# Linkee.net
KiCad netlist of a schematic drawn in EasyEDA
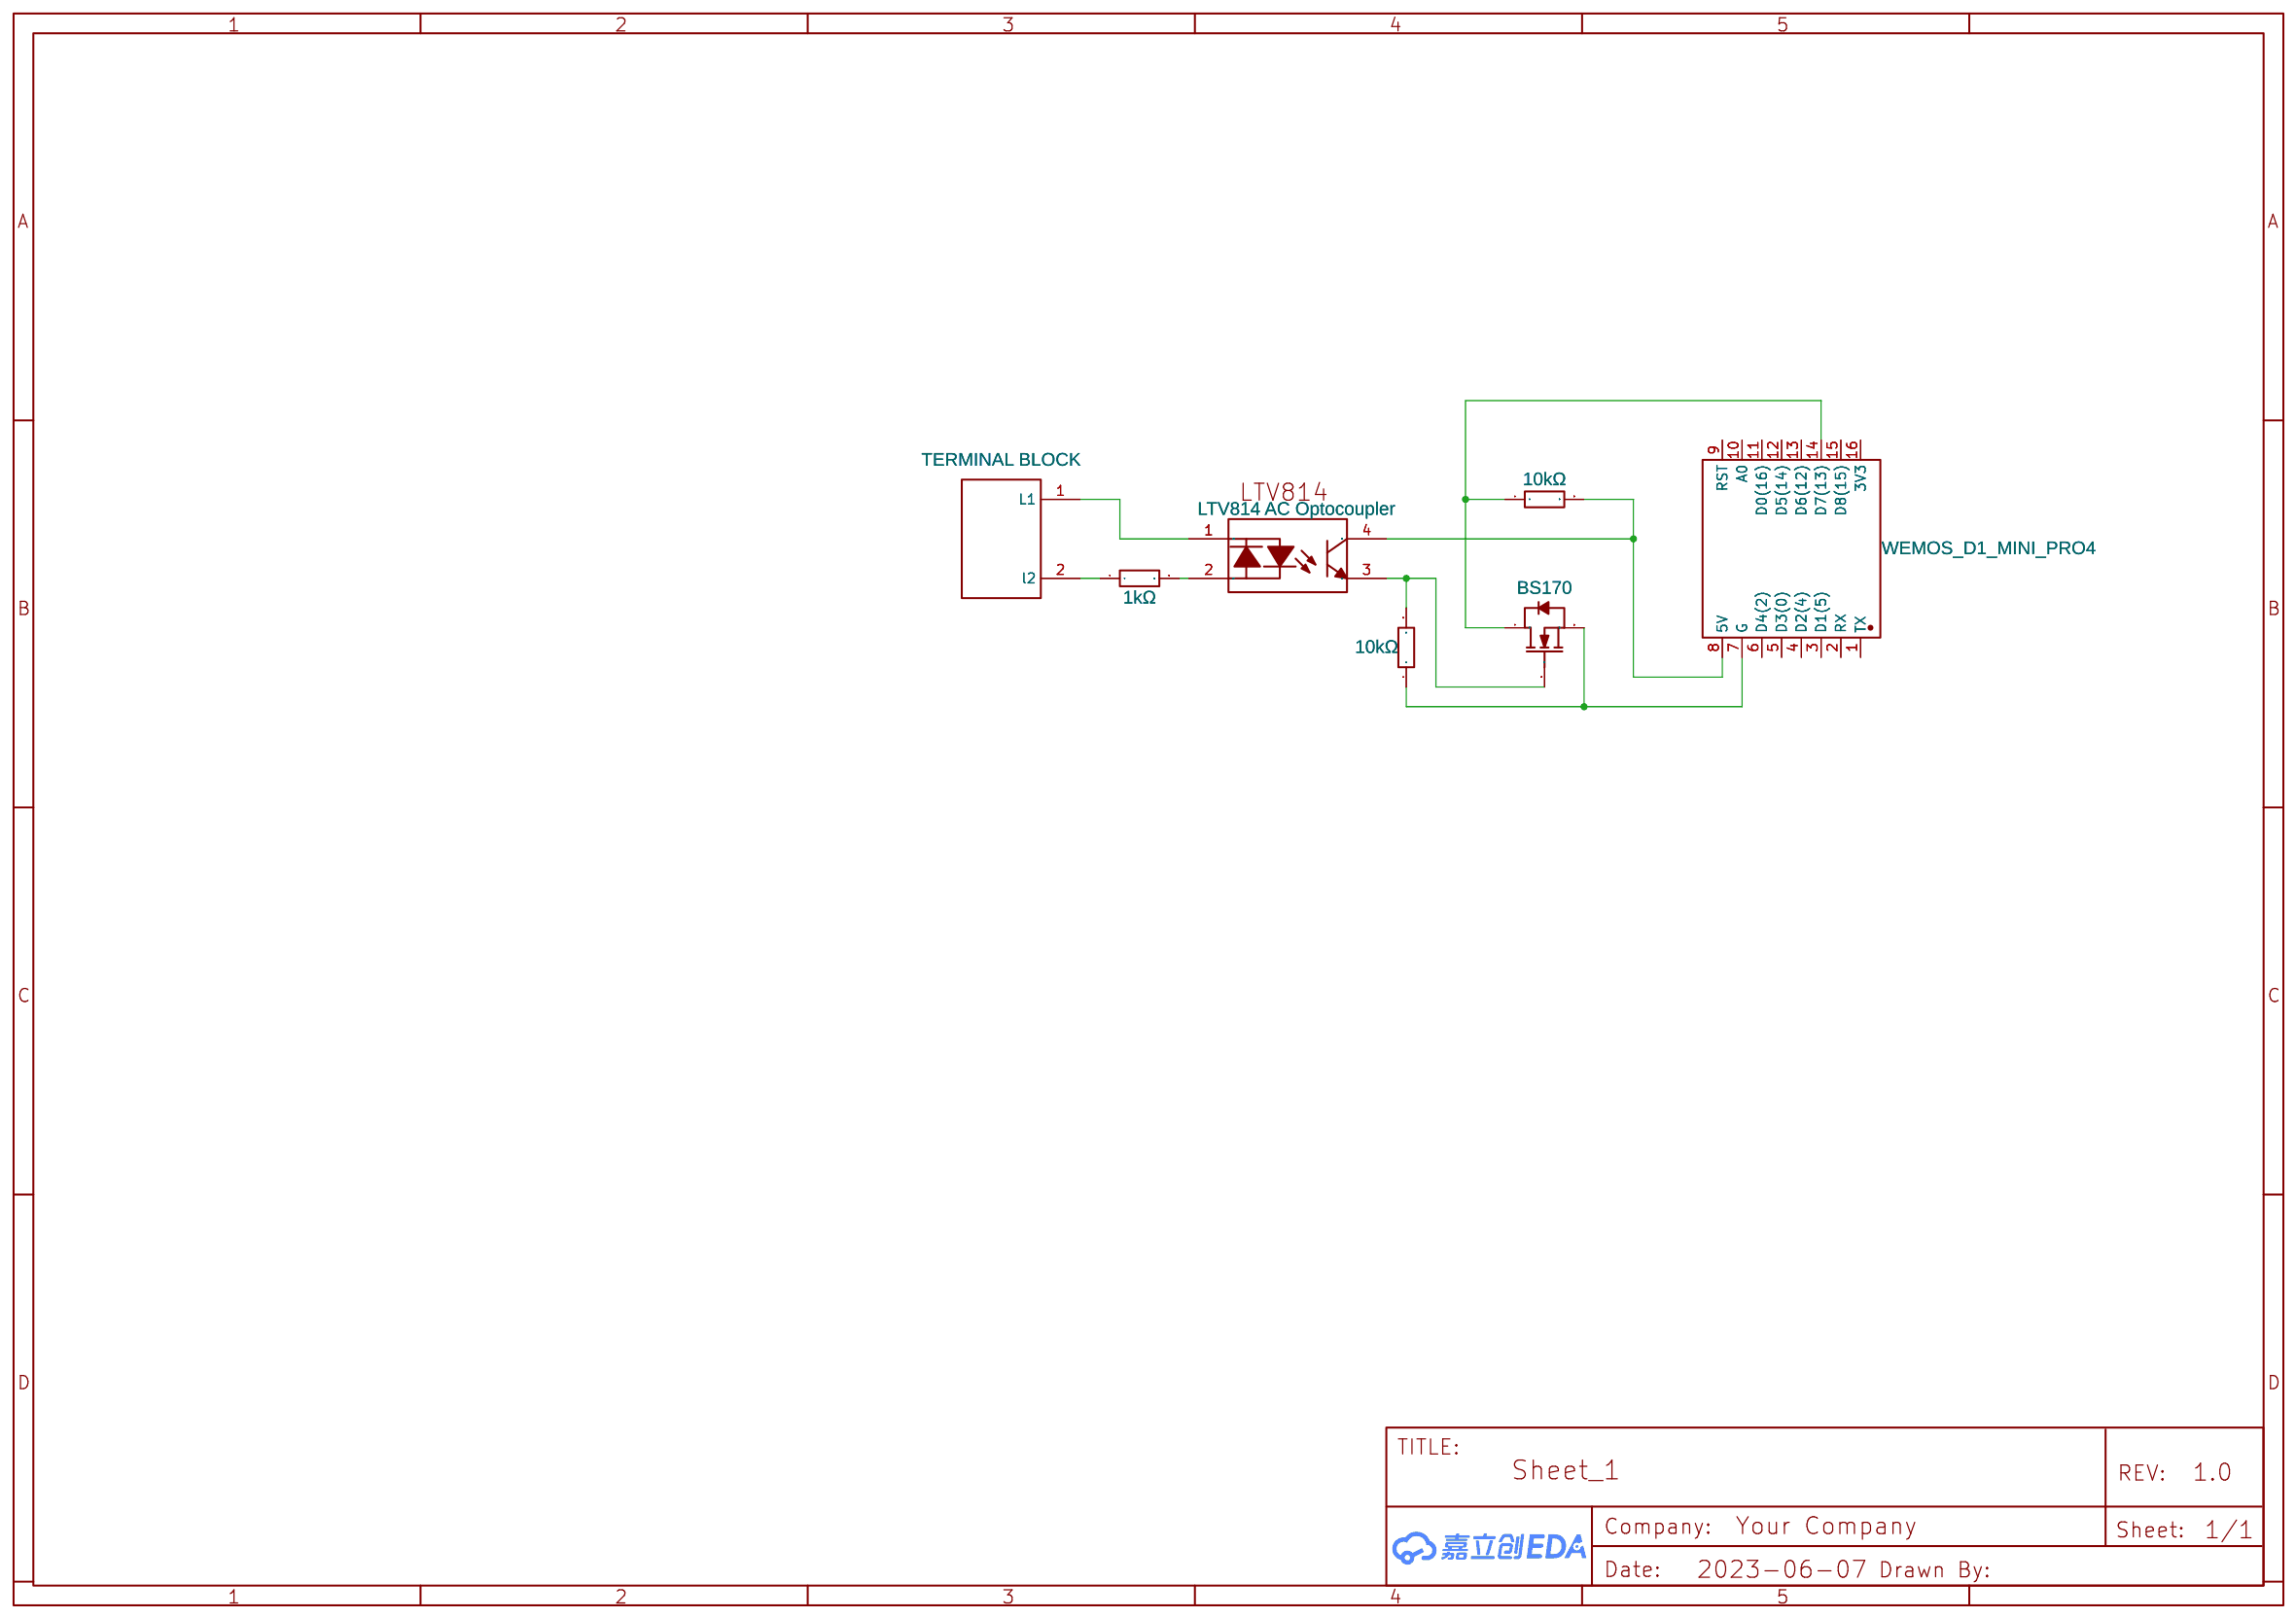
[diagram p0: schematic sheet]

(export (version "E")
  (design (tool "Eeschema 10.0.6"))
  (components
    (comp (ref "J1") (value "TERMINAL BLOCK") (libsource (lib "") (part "Bornier2")))
    (comp (ref "Q1")
      (value "BS170")
      (fields (field (name "Manufacturer") "onsemi(安森美)"))
      (libsource (lib "") (part "BS170"))
    )
    (comp (ref "R1")
      (value "1kΩ")
      (fields
        (field (name "Manufacturer Part") "0603WAF1001T5E")
        (field (name "Manufacturer") "UNI-ROYAL(厚声)")
      )
      (libsource (lib "") (part "0603WAF1001T5E"))
    )
    (comp (ref "R2")
      (value "10kΩ")
      (fields
        (field (name "Manufacturer Part") "0603WAF1002T5E")
        (field (name "Manufacturer") "UNI-ROYAL(厚声)")
      )
      (libsource (lib "") (part "0603WAF1002T5E_1"))
    )
    (comp (ref "R3")
      (value "10kΩ")
      (fields
        (field (name "Manufacturer Part") "0603WAF1002T5E")
        (field (name "Manufacturer") "UNI-ROYAL(厚声)")
      )
      (libsource (lib "") (part "0603WAF1002T5E"))
    )
    (comp (ref "U1")
      (value "WEMOS_D1_MINI_PRO4")
      (fields (field (name "Manufacturer Part") "Wemos_D1_mini_Pro4"))
      (libsource (lib "") (part "WEMOS_D1_MINI_PRO4"))
    )
    (comp (ref "U2")
      (value "LTV814 AC Optocoupler")
      (fields (field (name "Manufacturer Part") "SFH6206-3T") (field (name "Manufacturer") "VISHAY"))
      (libsource (lib "") (part "LTV814 AC Optocoupler"))
    )
  )
  (nets
    (net (code "1") (name "Net-(J1-L1)") (class "Default")
      (node (ref "J1") (pin "1") (pinfunction "L1_1") (pintype "unspecified"))
      (node (ref "U2") (pin "1") (pinfunction "A/C_1") (pintype "unspecified"))
    )
    (net (code "2") (name "Net-(J1-l2)") (class "Default")
      (node (ref "J1") (pin "2") (pinfunction "l2_2") (pintype "unspecified"))
      (node (ref "R1") (pin "1") (pinfunction "1_1") (pintype "input"))
    )
    (net (code "3") (name "Net-(Q1-D)") (class "Default")
      (node (ref "Q1") (pin "1") (pinfunction "D_1") (pintype "unspecified"))
      (node (ref "R3") (pin "1") (pinfunction "1_1") (pintype "input"))
      (node (ref "U1") (pin "14") (pinfunction "D7(13)_14") (pintype "unspecified"))
    )
    (net (code "4") (name "Net-(Q1-G)") (class "Default")
      (node (ref "Q1") (pin "2") (pinfunction "G_2") (pintype "unspecified"))
      (node (ref "R2") (pin "2") (pinfunction "2_2") (pintype "input"))
      (node (ref "U2") (pin "3") (pinfunction "EM_3") (pintype "unspecified"))
    )
    (net (code "5") (name "Net-(Q1-S)") (class "Default")
      (node (ref "Q1") (pin "3") (pinfunction "S_3") (pintype "unspecified"))
      (node (ref "R2") (pin "1") (pinfunction "1_1") (pintype "input"))
      (node (ref "U1") (pin "7") (pinfunction "G_7") (pintype "unspecified"))
    )
    (net (code "6") (name "Net-(U1-5V)") (class "Default")
      (node (ref "R3") (pin "2") (pinfunction "2_2") (pintype "input"))
      (node (ref "U1") (pin "8") (pinfunction "5V_8") (pintype "unspecified"))
      (node (ref "U2") (pin "4") (pinfunction "COL_4") (pintype "unspecified"))
    )
    (net (code "7") (name "Net-(U2-C{slash}A)") (class "Default")
      (node (ref "R1") (pin "2") (pinfunction "2_2") (pintype "input"))
      (node (ref "U2") (pin "2") (pinfunction "C/A_2") (pintype "unspecified"))
    )
    (net (code "8") (name "unconnected-(U1-3V3-Pad16)") (class "Default")
      (node (ref "U1") (pin "16") (pinfunction "3V3_16") (pintype "unspecified"))
    )
    (net (code "9") (name "unconnected-(U1-A0-Pad10)") (class "Default")
      (node (ref "U1") (pin "10") (pinfunction "A0_10") (pintype "unspecified"))
    )
    (net (code "10") (name "unconnected-(U1-D0(16)-Pad11)") (class "Default")
      (node (ref "U1") (pin "11") (pinfunction "D0(16)_11") (pintype "unspecified"))
    )
    (net (code "11") (name "unconnected-(U1-D1(5)-Pad3)") (class "Default")
      (node (ref "U1") (pin "3") (pinfunction "D1(5)_3") (pintype "unspecified"))
    )
    (net (code "12") (name "unconnected-(U1-D2(4)-Pad4)") (class "Default")
      (node (ref "U1") (pin "4") (pinfunction "D2(4)_4") (pintype "unspecified"))
    )
    (net (code "13") (name "unconnected-(U1-D3(0)-Pad5)") (class "Default")
      (node (ref "U1") (pin "5") (pinfunction "D3(0)_5") (pintype "unspecified"))
    )
    (net (code "14") (name "unconnected-(U1-D4(2)-Pad6)") (class "Default")
      (node (ref "U1") (pin "6") (pinfunction "D4(2)_6") (pintype "unspecified"))
    )
    (net (code "15") (name "unconnected-(U1-D5(14)-Pad12)") (class "Default")
      (node (ref "U1") (pin "12") (pinfunction "D5(14)_12") (pintype "unspecified"))
    )
    (net (code "16") (name "unconnected-(U1-D6(12)-Pad13)") (class "Default")
      (node (ref "U1") (pin "13") (pinfunction "D6(12)_13") (pintype "unspecified"))
    )
    (net (code "17") (name "unconnected-(U1-D8(15)-Pad15)") (class "Default")
      (node (ref "U1") (pin "15") (pinfunction "D8(15)_15") (pintype "unspecified"))
    )
    (net (code "18") (name "unconnected-(U1-RST-Pad9)") (class "Default")
      (node (ref "U1") (pin "9") (pinfunction "RST_9") (pintype "unspecified"))
    )
    (net (code "19") (name "unconnected-(U1-RX-Pad2)") (class "Default")
      (node (ref "U1") (pin "2") (pinfunction "RX_2") (pintype "unspecified"))
    )
    (net (code "20") (name "unconnected-(U1-TX-Pad1)") (class "Default")
      (node (ref "U1") (pin "1") (pinfunction "TX_1") (pintype "unspecified"))
    )
  )
)
